# Output_Schematic.net
KiCad netlist of a schematic drawn in Altium Designer
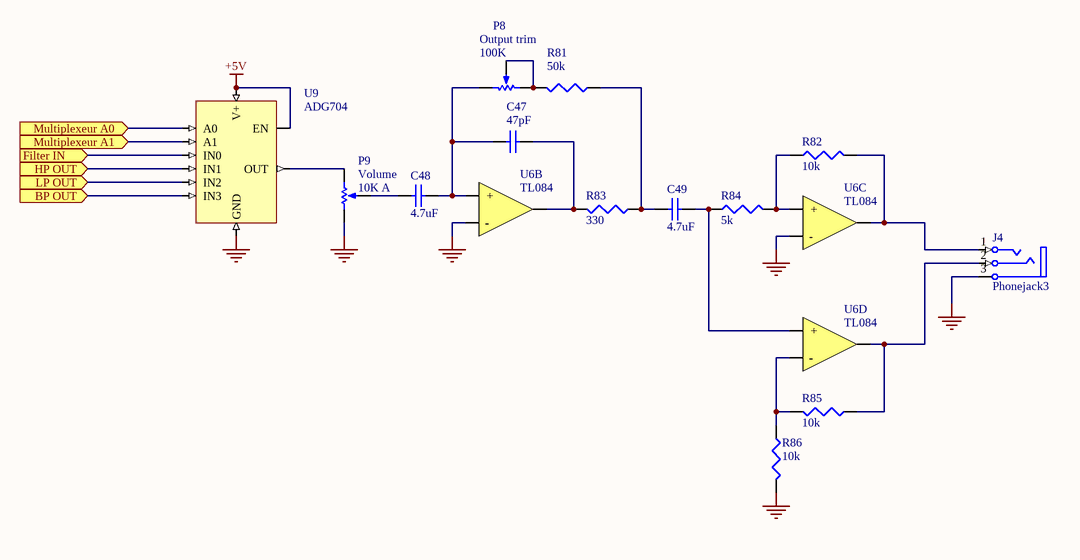
[diagram p0: Output.Schematic.SchDoc]

(export (version "E")
  (design (tool "Eeschema 10.0.6"))
  (components
    (comp (ref "C47")
      (value "47pF")
      (footprint "CAPC1608N")
      (description "Capacitor (Semiconductor SIM Model)")
      (fields (field (name "PUBLISHER") "Altium Limited"))
      (libsource (lib "Miscellaneous Devices") (part "Cap Semi"))
    )
    (comp (ref "C48")
      (value "4.7uF")
      (footprint "CAPC1608N")
      (description "Capacitor (Semiconductor SIM Model)")
      (fields (field (name "PUBLISHER") "Altium Limited"))
      (libsource (lib "Miscellaneous Devices") (part "Cap Semi"))
    )
    (comp (ref "C49")
      (value "4.7uF")
      (footprint "CAPC1608N")
      (description "Capacitor (Semiconductor SIM Model)")
      (fields (field (name "PUBLISHER") "Altium Limited"))
      (libsource (lib "Miscellaneous Devices") (part "Cap Semi"))
    )
    (comp (ref "J4")
      (value "Phonejack3")
      (footprint "Header 3")
      (description "Jack Socket, 1/4\" [6.5mm], Thru-Hole, Vertical, 3-Conductor Open Circuit (Non-Normalling)")
      (fields (field (name "PUBLISHER") "Altium Limited"))
      (libsource (lib "Miscellaneous Connectors") (part "Phonejack3"))
    )
    (comp (ref "P8")
      (value "Output trim")
      (footprint "BOURNS Trim pot")
      (description "Potentiometer")
      (fields (field (name "ALTIUM_VALUE") "100K") (field (name "PUBLISHER") "Altium Limited"))
      (libsource (lib "Miscellaneous Devices") (part "RPot"))
    )
    (comp (ref "P9")
      (value "Volume")
      (footprint "ALPS Potentiometer")
      (description "Potentiometer")
      (fields (field (name "ALTIUM_VALUE") "10K A") (field (name "PUBLISHER") "Altium Limited"))
      (libsource (lib "Miscellaneous Devices") (part "RPot"))
    )
    (comp (ref "R81")
      (value "50k")
      (footprint "CAPC1608N")
      (description "Resistor")
      (fields (field (name "PUBLISHER") "Altium Limited"))
      (libsource (lib "Miscellaneous Devices") (part "Res3"))
    )
    (comp (ref "R82")
      (value "10k")
      (footprint "CAPC1608N")
      (description "Resistor")
      (fields (field (name "PUBLISHER") "Altium Limited"))
      (libsource (lib "Miscellaneous Devices") (part "Res3"))
    )
    (comp (ref "R83")
      (value "330")
      (footprint "CAPC1608N")
      (description "Resistor")
      (fields (field (name "PUBLISHER") "Altium Limited"))
      (libsource (lib "Miscellaneous Devices") (part "Res3"))
    )
    (comp (ref "R84")
      (value "5k")
      (footprint "CAPC1608N")
      (description "Resistor")
      (fields (field (name "PUBLISHER") "Altium Limited"))
      (libsource (lib "Miscellaneous Devices") (part "Res3"))
    )
    (comp (ref "R85")
      (value "10k")
      (footprint "CAPC1608N")
      (description "Resistor")
      (fields (field (name "PUBLISHER") "Altium Limited"))
      (libsource (lib "Miscellaneous Devices") (part "Res3"))
    )
    (comp (ref "R86")
      (value "10k")
      (footprint "CAPC1608N")
      (description "Resistor")
      (fields (field (name "PUBLISHER") "Altium Limited"))
      (libsource (lib "Miscellaneous Devices") (part "Res3"))
    )
    (comp (ref "U6B")
      (value "TL084")
      (footprint "TL084 - 3pads")
      (libsource (lib "SynthyTwo.Components") (part "TL084"))
    )
    (comp (ref "U6C")
      (value "TL084")
      (footprint "TL084 - 3pads")
      (libsource (lib "SynthyTwo.Components") (part "TL084"))
    )
    (comp (ref "U6D")
      (value "TL084")
      (footprint "TL084 - 3pads")
      (libsource (lib "SynthyTwo.Components") (part "TL084"))
    )
    (comp (ref "U9")
      (value "ADG704")
      (footprint "ADG704")
      (libsource (lib "SynthyTwo.Components") (part "ADG704"))
    )
  )
  (nets
    (net (code "1") (name "+5V") (class "Default")
      (node (ref "U9") (pin "5") (pinfunction "EN_5") (pintype "passive"))
      (node (ref "U9") (pin "6") (pinfunction "V+_6") (pintype "input"))
    )
    (net (code "2") (name "/BP OUT") (class "Default")
      (node (ref "U9") (pin "7") (pinfunction "IN3_7") (pintype "input"))
    )
    (net (code "3") (name "/Filter IN") (class "Default")
      (node (ref "U9") (pin "2") (pinfunction "IN0_2") (pintype "input"))
    )
    (net (code "4") (name "/HP OUT") (class "Default")
      (node (ref "U9") (pin "9") (pinfunction "IN1_9") (pintype "input"))
    )
    (net (code "5") (name "/LP OUT") (class "Default")
      (node (ref "U9") (pin "4") (pinfunction "IN2_4") (pintype "input"))
    )
    (net (code "6") (name "/Multiplexeur A0") (class "Default")
      (node (ref "U9") (pin "1") (pinfunction "A0_1") (pintype "input"))
    )
    (net (code "7") (name "/Multiplexeur A1") (class "Default")
      (node (ref "U9") (pin "10") (pinfunction "A1_10") (pintype "input"))
    )
    (net (code "8") (name "GND") (class "Default")
      (node (ref "J4") (pin "3") (pinfunction "S_3") (pintype "power_in"))
      (node (ref "P9") (pin "1") (pinfunction "TOP_1") (pintype "passive"))
      (node (ref "R86") (pin "2") (pinfunction "2_2") (pintype "passive"))
      (node (ref "U6B") (pin "2") (pinfunction "-_2") (pintype "passive"))
      (node (ref "U6C") (pin "2") (pinfunction "-_2") (pintype "passive"))
      (node (ref "U9") (pin "3") (pinfunction "GND_3") (pintype "input"))
    )
    (net (code "9") (name "Net-(C49-Pad1)") (class "Default")
      (node (ref "C49") (pin "1") (pinfunction "1_1") (pintype "passive"))
      (node (ref "R81") (pin "1") (pinfunction "1_1") (pintype "passive"))
      (node (ref "R83") (pin "1") (pinfunction "1_1") (pintype "passive"))
    )
    (net (code "10") (name "Net-(J4-R)") (class "Default")
      (node (ref "J4") (pin "2") (pinfunction "R_2") (pintype "input"))
      (node (ref "R85") (pin "1") (pinfunction "1_1") (pintype "passive"))
      (node (ref "U6D") (pin "1") (pinfunction "OUT_1") (pintype "passive"))
    )
    (net (code "11") (name "Net-(J4-T)") (class "Default")
      (node (ref "J4") (pin "1") (pinfunction "T_1") (pintype "input"))
      (node (ref "R82") (pin "2") (pinfunction "2_2") (pintype "passive"))
      (node (ref "U6C") (pin "1") (pinfunction "OUT_1") (pintype "passive"))
    )
    (net (code "12") (name "Net-(P8-BOT)") (class "Default")
      (node (ref "P8") (pin "2") (pinfunction "BOT_2") (pintype "passive"))
      (node (ref "P8") (pin "3") (pinfunction "TAP_3") (pintype "passive"))
      (node (ref "R81") (pin "2") (pinfunction "2_2") (pintype "passive"))
    )
    (net (code "13") (name "Net-(P8-TOP)") (class "Default")
      (node (ref "C47") (pin "1") (pinfunction "1_1") (pintype "passive"))
      (node (ref "C48") (pin "2") (pinfunction "2_2") (pintype "passive"))
      (node (ref "P8") (pin "1") (pinfunction "TOP_1") (pintype "passive"))
      (node (ref "U6B") (pin "3") (pinfunction "+_3") (pintype "passive"))
    )
    (net (code "14") (name "Net-(P9-BOT)") (class "Default")
      (node (ref "P9") (pin "2") (pinfunction "BOT_2") (pintype "passive"))
      (node (ref "U9") (pin "8") (pinfunction "OUT_8") (pintype "output"))
    )
    (net (code "15") (name "Net-(P9-TAP)") (class "Default")
      (node (ref "C48") (pin "1") (pinfunction "1_1") (pintype "passive"))
      (node (ref "P9") (pin "3") (pinfunction "TAP_3") (pintype "passive"))
    )
    (net (code "16") (name "Net-(U6B-OUT)") (class "Default")
      (node (ref "C47") (pin "2") (pinfunction "2_2") (pintype "passive"))
      (node (ref "R83") (pin "2") (pinfunction "2_2") (pintype "passive"))
      (node (ref "U6B") (pin "1") (pinfunction "OUT_1") (pintype "passive"))
    )
    (net (code "17") (name "Net-(U6C-+)") (class "Default")
      (node (ref "R82") (pin "1") (pinfunction "1_1") (pintype "passive"))
      (node (ref "R84") (pin "2") (pinfunction "2_2") (pintype "passive"))
      (node (ref "U6C") (pin "3") (pinfunction "+_3") (pintype "passive"))
    )
    (net (code "18") (name "Net-(U6D-+)") (class "Default")
      (node (ref "C49") (pin "2") (pinfunction "2_2") (pintype "passive"))
      (node (ref "R84") (pin "1") (pinfunction "1_1") (pintype "passive"))
      (node (ref "U6D") (pin "3") (pinfunction "+_3") (pintype "passive"))
    )
    (net (code "19") (name "Net-(U6D--)") (class "Default")
      (node (ref "R85") (pin "2") (pinfunction "2_2") (pintype "passive"))
      (node (ref "R86") (pin "1") (pinfunction "1_1") (pintype "passive"))
      (node (ref "U6D") (pin "2") (pinfunction "-_2") (pintype "passive"))
    )
  )
)
